# e-Tapperhandpiece20.net
KiCad netlist of a schematic drawn in EAGLE
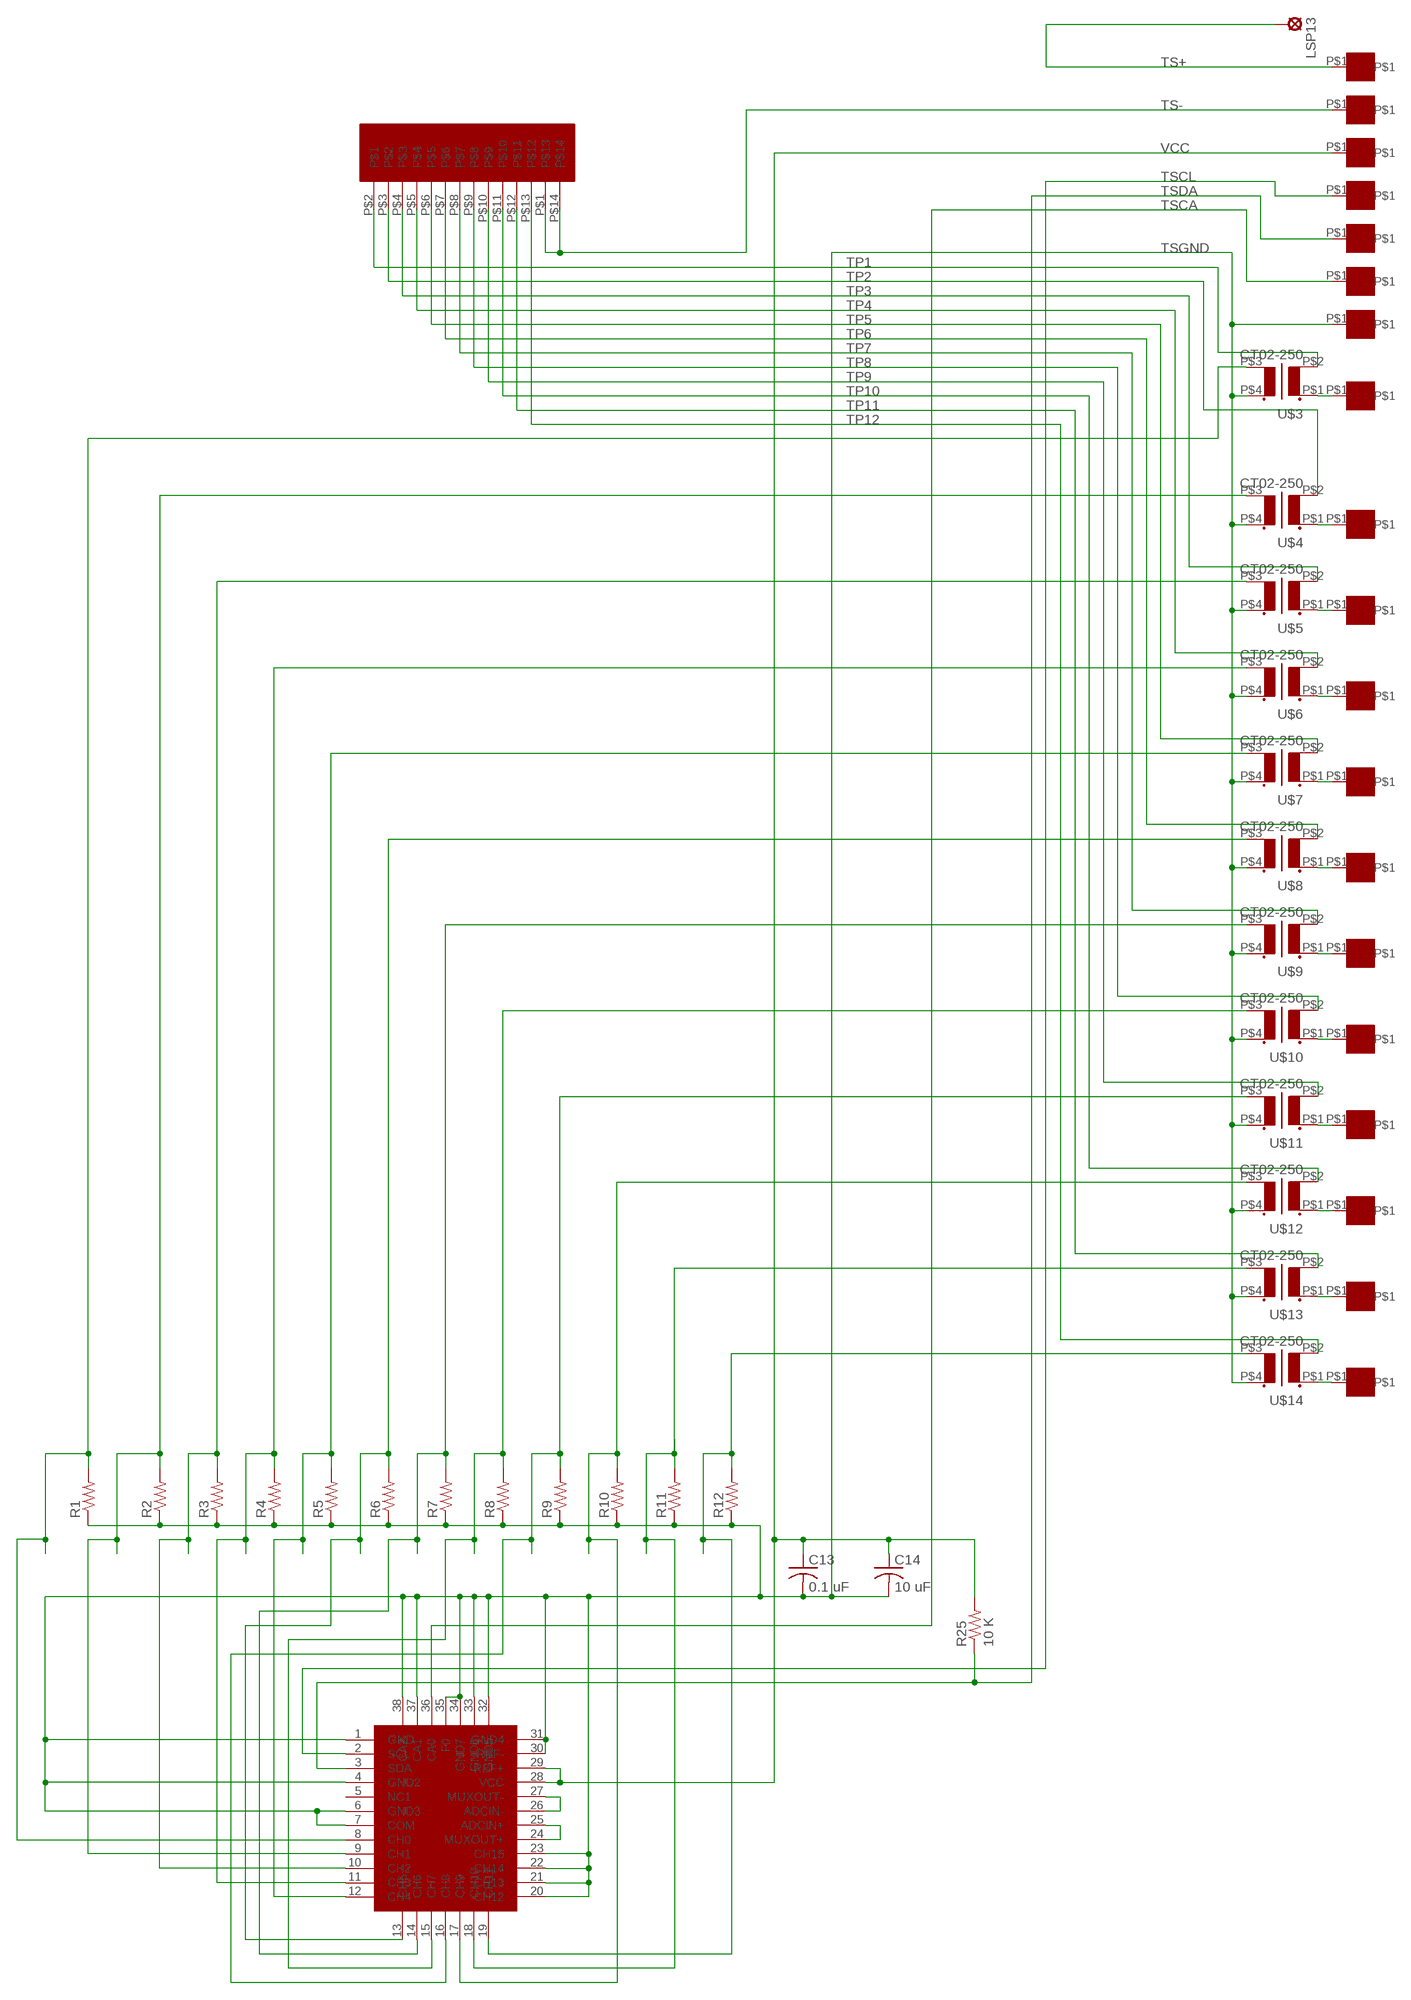
[diagram p0: schematic, sheet 1]

(export (version "E")
  (design (tool "Eeschema 10.0.6"))
  (components
    (comp (ref "C13")
      (value "0.1 uF")
      (footprint "eagle-import:C0603")
      (libsource (lib "eagle-import") (part "C-USC0603"))
    )
    (comp (ref "C14")
      (value "10 uF")
      (footprint "eagle-import:C0805")
      (libsource (lib "eagle-import") (part "C-USC0805"))
    )
    (comp (ref "LSP13")
      (value "SE11")
      (footprint "eagle-import:SE11")
      (libsource (lib "eagle-import") (part "SE11"))
    )
    (comp (ref "R1")
      (value "R-US_R0402")
      (footprint "eagle-import:R0402")
      (libsource (lib "eagle-import") (part "R-US_R0402"))
    )
    (comp (ref "R2")
      (value "R-US_R0402")
      (footprint "eagle-import:R0402")
      (libsource (lib "eagle-import") (part "R-US_R0402"))
    )
    (comp (ref "R3")
      (value "R-US_R0402")
      (footprint "eagle-import:R0402")
      (libsource (lib "eagle-import") (part "R-US_R0402"))
    )
    (comp (ref "R4")
      (value "R-US_R0402")
      (footprint "eagle-import:R0402")
      (libsource (lib "eagle-import") (part "R-US_R0402"))
    )
    (comp (ref "R5")
      (value "R-US_R0402")
      (footprint "eagle-import:R0402")
      (libsource (lib "eagle-import") (part "R-US_R0402"))
    )
    (comp (ref "R6")
      (value "R-US_R0402")
      (footprint "eagle-import:R0402")
      (libsource (lib "eagle-import") (part "R-US_R0402"))
    )
    (comp (ref "R7")
      (value "R-US_R0402")
      (footprint "eagle-import:R0402")
      (libsource (lib "eagle-import") (part "R-US_R0402"))
    )
    (comp (ref "R8")
      (value "R-US_R0402")
      (footprint "eagle-import:R0402")
      (libsource (lib "eagle-import") (part "R-US_R0402"))
    )
    (comp (ref "R9")
      (value "R-US_R0402")
      (footprint "eagle-import:R0402")
      (libsource (lib "eagle-import") (part "R-US_R0402"))
    )
    (comp (ref "R10")
      (value "R-US_R0402")
      (footprint "eagle-import:R0402")
      (libsource (lib "eagle-import") (part "R-US_R0402"))
    )
    (comp (ref "R11")
      (value "R-US_R0402")
      (footprint "eagle-import:R0402")
      (libsource (lib "eagle-import") (part "R-US_R0402"))
    )
    (comp (ref "R12")
      (value "R-US_R0402")
      (footprint "eagle-import:R0402")
      (libsource (lib "eagle-import") (part "R-US_R0402"))
    )
    (comp (ref "R25")
      (value "10 K")
      (footprint "eagle-import:R0402")
      (libsource (lib "eagle-import") (part "R-US_R0402"))
    )
    (comp (ref "TSP1")
      (value "ET1")
      (footprint "eagle-import:ET1")
      (libsource (lib "eagle-import") (part "ET1"))
    )
    (comp (ref "TSP2")
      (value "ET1")
      (footprint "eagle-import:ET1")
      (libsource (lib "eagle-import") (part "ET1"))
    )
    (comp (ref "TSP3")
      (value "ET1")
      (footprint "eagle-import:ET1")
      (libsource (lib "eagle-import") (part "ET1"))
    )
    (comp (ref "TSP4")
      (value "ET1")
      (footprint "eagle-import:ET1")
      (libsource (lib "eagle-import") (part "ET1"))
    )
    (comp (ref "TSP5")
      (value "ET1")
      (footprint "eagle-import:ET1")
      (libsource (lib "eagle-import") (part "ET1"))
    )
    (comp (ref "TSP6")
      (value "ET1")
      (footprint "eagle-import:ET1")
      (libsource (lib "eagle-import") (part "ET1"))
    )
    (comp (ref "TSP7")
      (value "ET1")
      (footprint "eagle-import:ET1")
      (libsource (lib "eagle-import") (part "ET1"))
    )
    (comp (ref "TSP8")
      (value "ET1")
      (footprint "eagle-import:ET1")
      (libsource (lib "eagle-import") (part "ET1"))
    )
    (comp (ref "TSP9")
      (value "ET1")
      (footprint "eagle-import:ET1")
      (libsource (lib "eagle-import") (part "ET1"))
    )
    (comp (ref "TSP10")
      (value "ET1")
      (footprint "eagle-import:ET1")
      (libsource (lib "eagle-import") (part "ET1"))
    )
    (comp (ref "TSP11")
      (value "ET1")
      (footprint "eagle-import:ET1")
      (libsource (lib "eagle-import") (part "ET1"))
    )
    (comp (ref "TSP12")
      (value "ET1")
      (footprint "eagle-import:ET1")
      (libsource (lib "eagle-import") (part "ET1"))
    )
    (comp (ref "TSP13")
      (value "ET1")
      (footprint "eagle-import:ET1")
      (libsource (lib "eagle-import") (part "ET1"))
    )
    (comp (ref "TSP14")
      (value "ET1")
      (footprint "eagle-import:ET1")
      (libsource (lib "eagle-import") (part "ET1"))
    )
    (comp (ref "TSP15")
      (value "ET1")
      (footprint "eagle-import:ET1")
      (libsource (lib "eagle-import") (part "ET1"))
    )
    (comp (ref "TSP16")
      (value "ET1")
      (footprint "eagle-import:ET1")
      (libsource (lib "eagle-import") (part "ET1"))
    )
    (comp (ref "TSP17")
      (value "ET1")
      (footprint "eagle-import:ET1")
      (libsource (lib "eagle-import") (part "ET1"))
    )
    (comp (ref "TSP18")
      (value "ET1")
      (footprint "eagle-import:ET1")
      (libsource (lib "eagle-import") (part "ET1"))
    )
    (comp (ref "TSP19")
      (value "ET1")
      (footprint "eagle-import:ET1")
      (libsource (lib "eagle-import") (part "ET1"))
    )
    (comp (ref "U$1")
      (value "LTC2497")
      (footprint "eagle-import:QFN38-5X7")
      (libsource (lib "eagle-import") (part "LTC2497"))
    )
    (comp (ref "U$2")
      (value "SS112D01")
      (footprint "eagle-import:SS112D01")
      (libsource (lib "eagle-import") (part "SS112D01"))
    )
    (comp (ref "U$3")
      (value "CT02-250")
      (footprint "eagle-import:CT02-250")
      (libsource (lib "eagle-import") (part "CT02-250"))
    )
    (comp (ref "U$4")
      (value "CT02-250")
      (footprint "eagle-import:CT02-250")
      (libsource (lib "eagle-import") (part "CT02-250"))
    )
    (comp (ref "U$5")
      (value "CT02-250")
      (footprint "eagle-import:CT02-250")
      (libsource (lib "eagle-import") (part "CT02-250"))
    )
    (comp (ref "U$6")
      (value "CT02-250")
      (footprint "eagle-import:CT02-250")
      (libsource (lib "eagle-import") (part "CT02-250"))
    )
    (comp (ref "U$7")
      (value "CT02-250")
      (footprint "eagle-import:CT02-250")
      (libsource (lib "eagle-import") (part "CT02-250"))
    )
    (comp (ref "U$8")
      (value "CT02-250")
      (footprint "eagle-import:CT02-250")
      (libsource (lib "eagle-import") (part "CT02-250"))
    )
    (comp (ref "U$9")
      (value "CT02-250")
      (footprint "eagle-import:CT02-250")
      (libsource (lib "eagle-import") (part "CT02-250"))
    )
    (comp (ref "U$10")
      (value "CT02-250")
      (footprint "eagle-import:CT02-250")
      (libsource (lib "eagle-import") (part "CT02-250"))
    )
    (comp (ref "U$11")
      (value "CT02-250")
      (footprint "eagle-import:CT02-250")
      (libsource (lib "eagle-import") (part "CT02-250"))
    )
    (comp (ref "U$12")
      (value "CT02-250")
      (footprint "eagle-import:CT02-250")
      (libsource (lib "eagle-import") (part "CT02-250"))
    )
    (comp (ref "U$13")
      (value "CT02-250")
      (footprint "eagle-import:CT02-250")
      (libsource (lib "eagle-import") (part "CT02-250"))
    )
    (comp (ref "U$14")
      (value "CT02-250")
      (footprint "eagle-import:CT02-250")
      (libsource (lib "eagle-import") (part "CT02-250"))
    )
  )
  (nets
    (net (code "1") (name "/TP1") (class "Default")
      (node (ref "U$2") (pin "P$2") (pinfunction "P$1_P$2") (pintype "bidirectional"))
      (node (ref "U$3") (pin "P$2") (pinfunction "P2_P$2") (pintype "passive"))
    )
    (net (code "2") (name "/TP2") (class "Default")
      (node (ref "U$2") (pin "P$3") (pinfunction "P$2_P$3") (pintype "bidirectional"))
      (node (ref "U$4") (pin "P$2") (pinfunction "P2_P$2") (pintype "passive"))
    )
    (net (code "3") (name "/TP3") (class "Default")
      (node (ref "U$2") (pin "P$4") (pinfunction "P$3_P$4") (pintype "bidirectional"))
      (node (ref "U$5") (pin "P$2") (pinfunction "P2_P$2") (pintype "passive"))
    )
    (net (code "4") (name "/TP4") (class "Default")
      (node (ref "U$2") (pin "P$5") (pinfunction "P$4_P$5") (pintype "bidirectional"))
      (node (ref "U$6") (pin "P$2") (pinfunction "P2_P$2") (pintype "passive"))
    )
    (net (code "5") (name "/TP5") (class "Default")
      (node (ref "U$2") (pin "P$6") (pinfunction "P$5_P$6") (pintype "bidirectional"))
      (node (ref "U$7") (pin "P$2") (pinfunction "P2_P$2") (pintype "passive"))
    )
    (net (code "6") (name "/TP6") (class "Default")
      (node (ref "U$2") (pin "P$7") (pinfunction "P$6_P$7") (pintype "bidirectional"))
      (node (ref "U$8") (pin "P$2") (pinfunction "P2_P$2") (pintype "passive"))
    )
    (net (code "7") (name "/TP7") (class "Default")
      (node (ref "U$2") (pin "P$8") (pinfunction "P$7_P$8") (pintype "bidirectional"))
      (node (ref "U$9") (pin "P$2") (pinfunction "P2_P$2") (pintype "passive"))
    )
    (net (code "8") (name "/TP8") (class "Default")
      (node (ref "U$10") (pin "P$2") (pinfunction "P2_P$2") (pintype "passive"))
      (node (ref "U$2") (pin "P$9") (pinfunction "P$8_P$9") (pintype "bidirectional"))
    )
    (net (code "9") (name "/TP9") (class "Default")
      (node (ref "U$11") (pin "P$2") (pinfunction "P2_P$2") (pintype "passive"))
      (node (ref "U$2") (pin "P$10") (pinfunction "P$9_P$10") (pintype "bidirectional"))
    )
    (net (code "10") (name "/TP10") (class "Default")
      (node (ref "U$12") (pin "P$2") (pinfunction "P2_P$2") (pintype "passive"))
      (node (ref "U$2") (pin "P$11") (pinfunction "P$10_P$11") (pintype "bidirectional"))
    )
    (net (code "11") (name "/TP11") (class "Default")
      (node (ref "U$13") (pin "P$2") (pinfunction "P2_P$2") (pintype "passive"))
      (node (ref "U$2") (pin "P$12") (pinfunction "P$11_P$12") (pintype "bidirectional"))
    )
    (net (code "12") (name "/TP12") (class "Default")
      (node (ref "U$14") (pin "P$2") (pinfunction "P2_P$2") (pintype "passive"))
      (node (ref "U$2") (pin "P$13") (pinfunction "P$12_P$13") (pintype "bidirectional"))
    )
    (net (code "13") (name "/TS+") (class "Default")
      (node (ref "LSP13") (pin "MP") (pinfunction "MP_MP") (pintype "passive"))
      (node (ref "TSP13") (pin "P$1") (pinfunction "P$1_P$1") (pintype "bidirectional"))
    )
    (net (code "14") (name "/TS-") (class "Default")
      (node (ref "TSP14") (pin "P$1") (pinfunction "P$1_P$1") (pintype "bidirectional"))
      (node (ref "U$2") (pin "P$1") (pinfunction "P$13_P$1") (pintype "bidirectional"))
      (node (ref "U$2") (pin "P$14") (pinfunction "P$14_P$14") (pintype "bidirectional"))
    )
    (net (code "15") (name "/TSCA") (class "Default")
      (node (ref "TSP18") (pin "P$1") (pinfunction "P$1_P$1") (pintype "bidirectional"))
      (node (ref "U$1") (pin "36") (pinfunction "CA0_36") (pintype "bidirectional"))
    )
    (net (code "16") (name "/TSCL") (class "Default")
      (node (ref "TSP16") (pin "P$1") (pinfunction "P$1_P$1") (pintype "bidirectional"))
      (node (ref "U$1") (pin "2") (pinfunction "SCL_2") (pintype "bidirectional"))
    )
    (net (code "17") (name "/TSDA") (class "Default")
      (node (ref "R25") (pin "1") (pinfunction "1_1") (pintype "passive"))
      (node (ref "TSP17") (pin "P$1") (pinfunction "P$1_P$1") (pintype "bidirectional"))
      (node (ref "U$1") (pin "3") (pinfunction "SDA_3") (pintype "bidirectional"))
    )
    (net (code "18") (name "/TSGND") (class "Default")
      (node (ref "C13") (pin "2") (pinfunction "2_2") (pintype "passive"))
      (node (ref "C14") (pin "2") (pinfunction "2_2") (pintype "passive"))
      (node (ref "R1") (pin "1") (pinfunction "1_1") (pintype "passive"))
      (node (ref "R10") (pin "1") (pinfunction "1_1") (pintype "passive"))
      (node (ref "R11") (pin "1") (pinfunction "1_1") (pintype "passive"))
      (node (ref "R12") (pin "1") (pinfunction "1_1") (pintype "passive"))
      (node (ref "R2") (pin "1") (pinfunction "1_1") (pintype "passive"))
      (node (ref "R3") (pin "1") (pinfunction "1_1") (pintype "passive"))
      (node (ref "R4") (pin "1") (pinfunction "1_1") (pintype "passive"))
      (node (ref "R5") (pin "1") (pinfunction "1_1") (pintype "passive"))
      (node (ref "R6") (pin "1") (pinfunction "1_1") (pintype "passive"))
      (node (ref "R7") (pin "1") (pinfunction "1_1") (pintype "passive"))
      (node (ref "R8") (pin "1") (pinfunction "1_1") (pintype "passive"))
      (node (ref "R9") (pin "1") (pinfunction "1_1") (pintype "passive"))
      (node (ref "TSP19") (pin "P$1") (pinfunction "P$1_P$1") (pintype "bidirectional"))
      (node (ref "U$1") (pin "1") (pinfunction "GND_1") (pintype "power_in"))
      (node (ref "U$1") (pin "20") (pinfunction "CH12_20") (pintype "input"))
      (node (ref "U$1") (pin "21") (pinfunction "CH13_21") (pintype "input"))
      (node (ref "U$1") (pin "22") (pinfunction "CH14_22") (pintype "input"))
      (node (ref "U$1") (pin "23") (pinfunction "CH15_23") (pintype "input"))
      (node (ref "U$1") (pin "30") (pinfunction "REF-_30") (pintype "bidirectional"))
      (node (ref "U$1") (pin "31") (pinfunction "GND4_31") (pintype "power_in"))
      (node (ref "U$1") (pin "32") (pinfunction "GND5_32") (pintype "power_in"))
      (node (ref "U$1") (pin "33") (pinfunction "GND6_33") (pintype "power_in"))
      (node (ref "U$1") (pin "34") (pinfunction "GND7_34") (pintype "power_in"))
      (node (ref "U$1") (pin "35") (pinfunction "F0_35") (pintype "bidirectional"))
      (node (ref "U$1") (pin "37") (pinfunction "CA1_37") (pintype "bidirectional"))
      (node (ref "U$1") (pin "38") (pinfunction "CA2_38") (pintype "bidirectional"))
      (node (ref "U$1") (pin "4") (pinfunction "GND2_4") (pintype "power_in"))
      (node (ref "U$1") (pin "6") (pinfunction "GND3_6") (pintype "power_in"))
      (node (ref "U$1") (pin "7") (pinfunction "COM_7") (pintype "power_in"))
      (node (ref "U$10") (pin "P$4") (pinfunction "S1_P$4") (pintype "passive"))
      (node (ref "U$11") (pin "P$4") (pinfunction "S1_P$4") (pintype "passive"))
      (node (ref "U$12") (pin "P$4") (pinfunction "S1_P$4") (pintype "passive"))
      (node (ref "U$13") (pin "P$4") (pinfunction "S1_P$4") (pintype "passive"))
      (node (ref "U$14") (pin "P$4") (pinfunction "S1_P$4") (pintype "passive"))
      (node (ref "U$3") (pin "P$4") (pinfunction "S1_P$4") (pintype "passive"))
      (node (ref "U$4") (pin "P$4") (pinfunction "S1_P$4") (pintype "passive"))
      (node (ref "U$5") (pin "P$4") (pinfunction "S1_P$4") (pintype "passive"))
      (node (ref "U$6") (pin "P$4") (pinfunction "S1_P$4") (pintype "passive"))
      (node (ref "U$7") (pin "P$4") (pinfunction "S1_P$4") (pintype "passive"))
      (node (ref "U$8") (pin "P$4") (pinfunction "S1_P$4") (pintype "passive"))
      (node (ref "U$9") (pin "P$4") (pinfunction "S1_P$4") (pintype "passive"))
    )
    (net (code "19") (name "/VCC") (class "Default")
      (node (ref "C13") (pin "1") (pinfunction "1_1") (pintype "passive"))
      (node (ref "C14") (pin "1") (pinfunction "1_1") (pintype "passive"))
      (node (ref "R25") (pin "2") (pinfunction "2_2") (pintype "passive"))
      (node (ref "TSP15") (pin "P$1") (pinfunction "P$1_P$1") (pintype "bidirectional"))
      (node (ref "U$1") (pin "28") (pinfunction "VCC_28") (pintype "power_in"))
      (node (ref "U$1") (pin "29") (pinfunction "REF+_29") (pintype "bidirectional"))
    )
    (net (code "20") (name "Net-(U$1-ADCIN+)") (class "Default")
      (node (ref "U$1") (pin "24") (pinfunction "MUXOUT+_24") (pintype "bidirectional"))
      (node (ref "U$1") (pin "25") (pinfunction "ADCIN+_25") (pintype "bidirectional"))
    )
    (net (code "21") (name "Net-(U$1-ADCIN-)") (class "Default")
      (node (ref "U$1") (pin "26") (pinfunction "ADCIN-_26") (pintype "bidirectional"))
      (node (ref "U$1") (pin "27") (pinfunction "MUXOUT-_27") (pintype "bidirectional"))
    )
    (net (code "22") (name "Net-(U$1-CH0)") (class "Default")
      (node (ref "R1") (pin "2") (pinfunction "2_2") (pintype "passive"))
      (node (ref "U$1") (pin "8") (pinfunction "CH0_8") (pintype "input"))
      (node (ref "U$3") (pin "P$3") (pinfunction "S2_P$3") (pintype "passive"))
    )
    (net (code "23") (name "Net-(U$1-CH1)") (class "Default")
      (node (ref "R2") (pin "2") (pinfunction "2_2") (pintype "passive"))
      (node (ref "U$1") (pin "9") (pinfunction "CH1_9") (pintype "input"))
      (node (ref "U$4") (pin "P$3") (pinfunction "S2_P$3") (pintype "passive"))
    )
    (net (code "24") (name "Net-(U$1-CH2)") (class "Default")
      (node (ref "R3") (pin "2") (pinfunction "2_2") (pintype "passive"))
      (node (ref "U$1") (pin "10") (pinfunction "CH2_10") (pintype "input"))
      (node (ref "U$5") (pin "P$3") (pinfunction "S2_P$3") (pintype "passive"))
    )
    (net (code "25") (name "Net-(U$1-CH3)") (class "Default")
      (node (ref "R4") (pin "2") (pinfunction "2_2") (pintype "passive"))
      (node (ref "U$1") (pin "11") (pinfunction "CH3_11") (pintype "input"))
      (node (ref "U$6") (pin "P$3") (pinfunction "S2_P$3") (pintype "passive"))
    )
    (net (code "26") (name "Net-(U$1-CH4)") (class "Default")
      (node (ref "R5") (pin "2") (pinfunction "2_2") (pintype "passive"))
      (node (ref "U$1") (pin "12") (pinfunction "CH4_12") (pintype "input"))
      (node (ref "U$7") (pin "P$3") (pinfunction "S2_P$3") (pintype "passive"))
    )
    (net (code "27") (name "Net-(U$1-CH5)") (class "Default")
      (node (ref "R6") (pin "2") (pinfunction "2_2") (pintype "passive"))
      (node (ref "U$1") (pin "13") (pinfunction "CH5_13") (pintype "input"))
      (node (ref "U$8") (pin "P$3") (pinfunction "S2_P$3") (pintype "passive"))
    )
    (net (code "28") (name "Net-(U$1-CH6)") (class "Default")
      (node (ref "R7") (pin "2") (pinfunction "2_2") (pintype "passive"))
      (node (ref "U$1") (pin "14") (pinfunction "CH6_14") (pintype "input"))
      (node (ref "U$9") (pin "P$3") (pinfunction "S2_P$3") (pintype "passive"))
    )
    (net (code "29") (name "Net-(U$1-CH7)") (class "Default")
      (node (ref "R8") (pin "2") (pinfunction "2_2") (pintype "passive"))
      (node (ref "U$1") (pin "15") (pinfunction "CH7_15") (pintype "input"))
      (node (ref "U$10") (pin "P$3") (pinfunction "S2_P$3") (pintype "passive"))
    )
    (net (code "30") (name "Net-(U$1-CH8)") (class "Default")
      (node (ref "R9") (pin "2") (pinfunction "2_2") (pintype "passive"))
      (node (ref "U$1") (pin "16") (pinfunction "CH8_16") (pintype "input"))
      (node (ref "U$11") (pin "P$3") (pinfunction "S2_P$3") (pintype "passive"))
    )
    (net (code "31") (name "Net-(U$1-CH9)") (class "Default")
      (node (ref "R10") (pin "2") (pinfunction "2_2") (pintype "passive"))
      (node (ref "U$1") (pin "17") (pinfunction "CH9_17") (pintype "input"))
      (node (ref "U$12") (pin "P$3") (pinfunction "S2_P$3") (pintype "passive"))
    )
    (net (code "32") (name "Net-(U$1-CH10)") (class "Default")
      (node (ref "R11") (pin "2") (pinfunction "2_2") (pintype "passive"))
      (node (ref "U$1") (pin "18") (pinfunction "CH10_18") (pintype "input"))
      (node (ref "U$13") (pin "P$3") (pinfunction "S2_P$3") (pintype "passive"))
    )
    (net (code "33") (name "Net-(U$1-CH11)") (class "Default")
      (node (ref "R12") (pin "2") (pinfunction "2_2") (pintype "passive"))
      (node (ref "U$1") (pin "19") (pinfunction "CH11_19") (pintype "input"))
      (node (ref "U$14") (pin "P$3") (pinfunction "S2_P$3") (pintype "passive"))
    )
    (net (code "34") (name "Net-(U$3-P1)") (class "Default")
      (node (ref "TSP1") (pin "P$1") (pinfunction "P$1_P$1") (pintype "bidirectional"))
      (node (ref "U$3") (pin "P$1") (pinfunction "P1_P$1") (pintype "passive"))
    )
    (net (code "35") (name "Net-(U$4-P1)") (class "Default")
      (node (ref "TSP2") (pin "P$1") (pinfunction "P$1_P$1") (pintype "bidirectional"))
      (node (ref "U$4") (pin "P$1") (pinfunction "P1_P$1") (pintype "passive"))
    )
    (net (code "36") (name "Net-(U$5-P1)") (class "Default")
      (node (ref "TSP3") (pin "P$1") (pinfunction "P$1_P$1") (pintype "bidirectional"))
      (node (ref "U$5") (pin "P$1") (pinfunction "P1_P$1") (pintype "passive"))
    )
    (net (code "37") (name "Net-(U$6-P1)") (class "Default")
      (node (ref "TSP4") (pin "P$1") (pinfunction "P$1_P$1") (pintype "bidirectional"))
      (node (ref "U$6") (pin "P$1") (pinfunction "P1_P$1") (pintype "passive"))
    )
    (net (code "38") (name "Net-(U$7-P1)") (class "Default")
      (node (ref "TSP5") (pin "P$1") (pinfunction "P$1_P$1") (pintype "bidirectional"))
      (node (ref "U$7") (pin "P$1") (pinfunction "P1_P$1") (pintype "passive"))
    )
    (net (code "39") (name "Net-(U$8-P1)") (class "Default")
      (node (ref "TSP6") (pin "P$1") (pinfunction "P$1_P$1") (pintype "bidirectional"))
      (node (ref "U$8") (pin "P$1") (pinfunction "P1_P$1") (pintype "passive"))
    )
    (net (code "40") (name "Net-(U$9-P1)") (class "Default")
      (node (ref "TSP7") (pin "P$1") (pinfunction "P$1_P$1") (pintype "bidirectional"))
      (node (ref "U$9") (pin "P$1") (pinfunction "P1_P$1") (pintype "passive"))
    )
    (net (code "41") (name "Net-(U$10-P1)") (class "Default")
      (node (ref "TSP8") (pin "P$1") (pinfunction "P$1_P$1") (pintype "bidirectional"))
      (node (ref "U$10") (pin "P$1") (pinfunction "P1_P$1") (pintype "passive"))
    )
    (net (code "42") (name "Net-(U$11-P1)") (class "Default")
      (node (ref "TSP9") (pin "P$1") (pinfunction "P$1_P$1") (pintype "bidirectional"))
      (node (ref "U$11") (pin "P$1") (pinfunction "P1_P$1") (pintype "passive"))
    )
    (net (code "43") (name "Net-(U$12-P1)") (class "Default")
      (node (ref "TSP10") (pin "P$1") (pinfunction "P$1_P$1") (pintype "bidirectional"))
      (node (ref "U$12") (pin "P$1") (pinfunction "P1_P$1") (pintype "passive"))
    )
    (net (code "44") (name "Net-(U$13-P1)") (class "Default")
      (node (ref "TSP11") (pin "P$1") (pinfunction "P$1_P$1") (pintype "bidirectional"))
      (node (ref "U$13") (pin "P$1") (pinfunction "P1_P$1") (pintype "passive"))
    )
    (net (code "45") (name "Net-(U$14-P1)") (class "Default")
      (node (ref "TSP12") (pin "P$1") (pinfunction "P$1_P$1") (pintype "bidirectional"))
      (node (ref "U$14") (pin "P$1") (pinfunction "P1_P$1") (pintype "passive"))
    )
    (net (code "46") (name "unconnected-(U$1-NC1-Pad5)") (class "Default")
      (node (ref "U$1") (pin "5") (pinfunction "NC1_5") (pintype "no_connect"))
    )
  )
)
